# FlyballETS-MBD.net
KiCad netlist of a schematic drawn in EAGLE
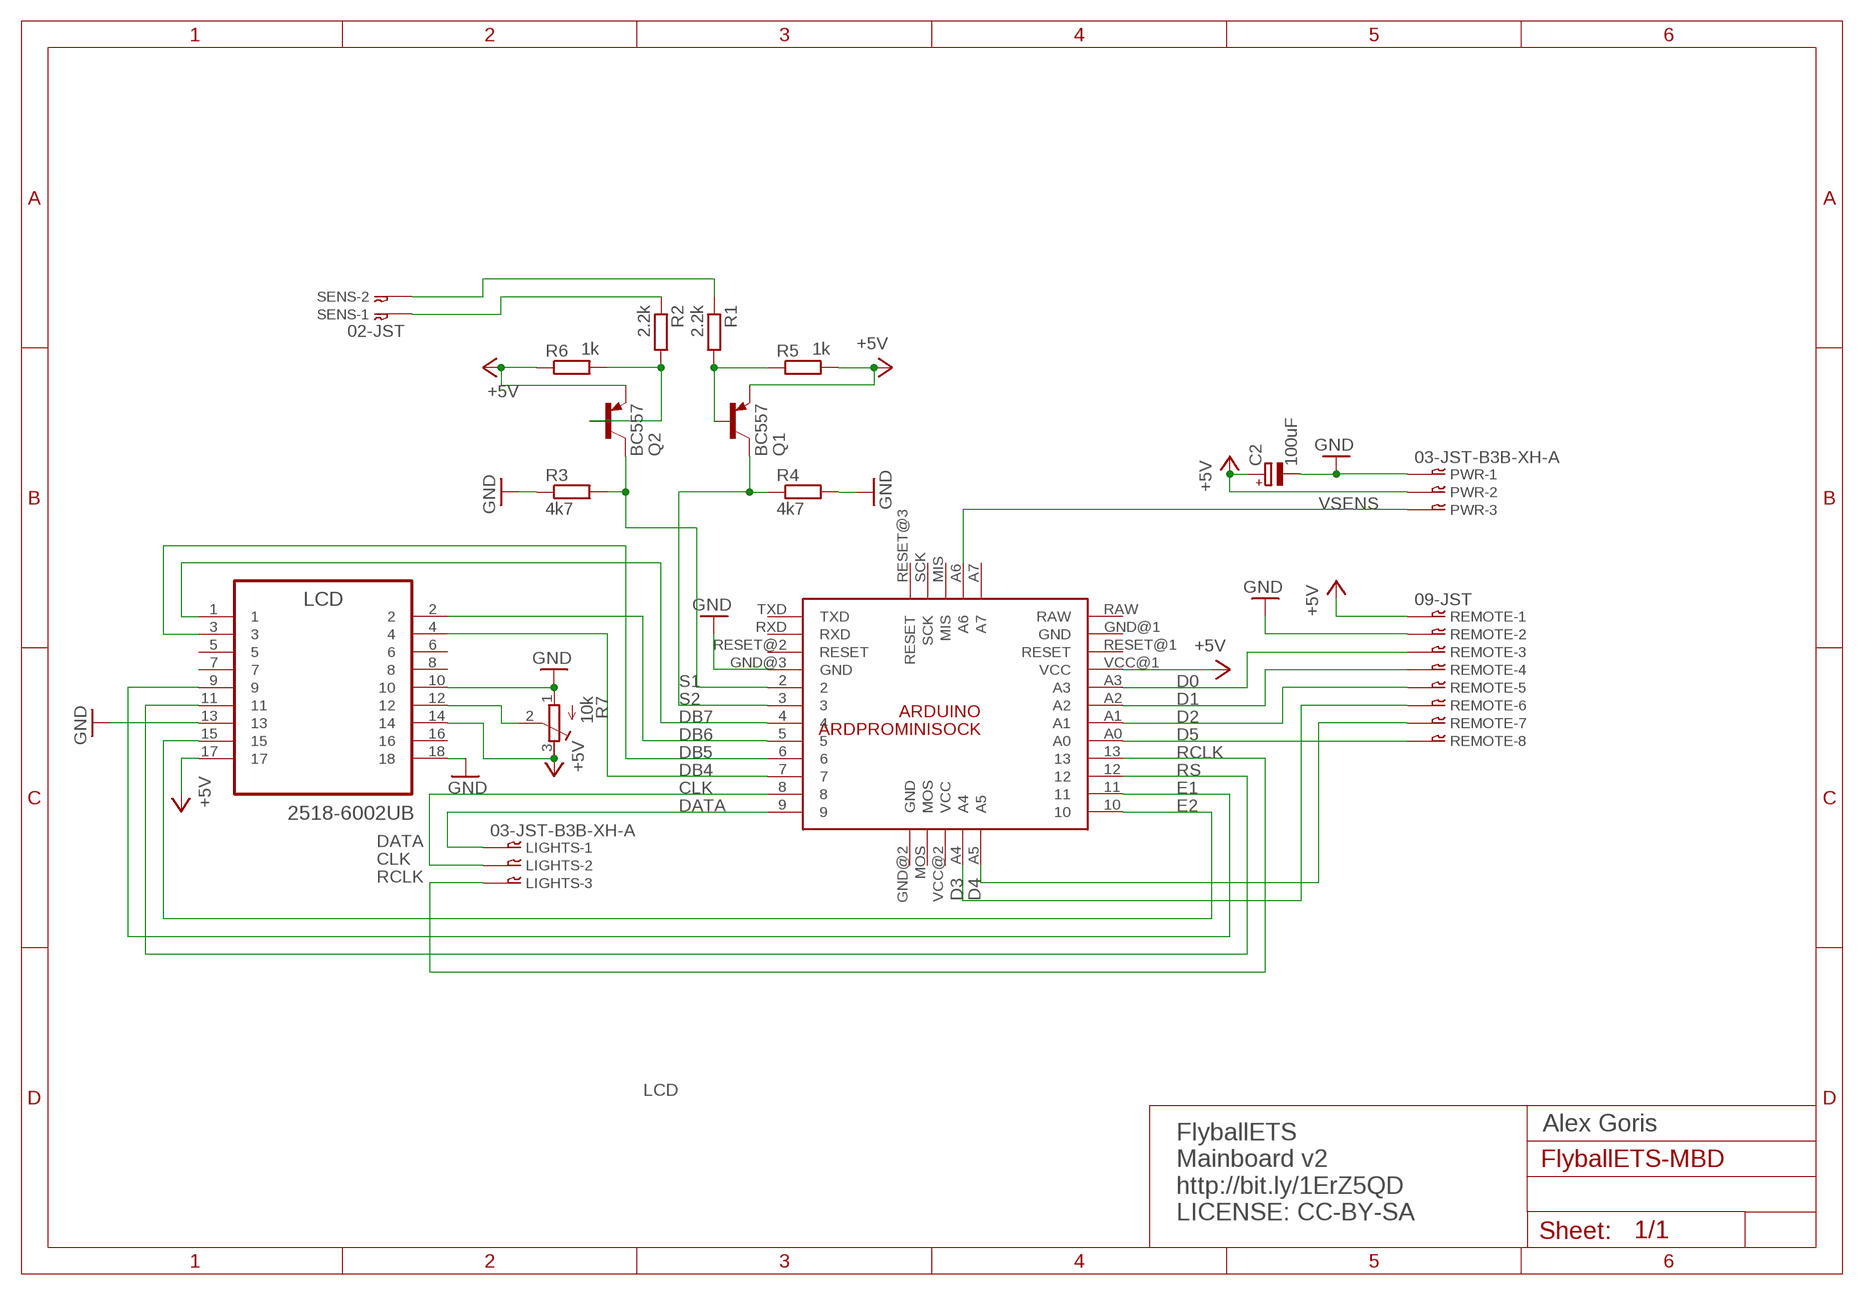
[diagram p0: schematic, sheet 1]

(export (version "E")
  (design (tool "Eeschema 10.0.6"))
  (components
    (comp (ref "ARDUINO")
      (value "ARDPROMINISOCK")
      (footprint "eagle-import:ARDPROMINISOCK")
      (libsource (lib "eagle-import") (part "ARDPROMINISOCK"))
    )
    (comp (ref "C2")
      (value "100uF")
      (footprint "eagle-import:E2,5-6E")
      (libsource (lib "eagle-import") (part "CPOL-EUE2,5-6E"))
    )
    (comp (ref "LCD")
      (value "2518-6002UB")
      (footprint "eagle-import:3M_2518-6002UB")
      (libsource (lib "eagle-import") (part "2518-6002UB"))
    )
    (comp (ref "LIGHTS")
      (value "03-JST-B3B-XH-A")
      (footprint "eagle-import:B3B-XH")
      (libsource (lib "eagle-import") (part "03-JST-B3B-XH-A"))
    )
    (comp (ref "PWR")
      (value "03-JST-B3B-XH-A")
      (footprint "eagle-import:B3B-XH")
      (libsource (lib "eagle-import") (part "03-JST-B3B-XH-A"))
    )
    (comp (ref "Q1")
      (value "BC557")
      (footprint "eagle-import:TO92")
      (libsource (lib "eagle-import") (part "BC557"))
    )
    (comp (ref "Q2")
      (value "BC557")
      (footprint "eagle-import:TO92")
      (libsource (lib "eagle-import") (part "BC557"))
    )
    (comp (ref "R1")
      (value "2.2k")
      (footprint "eagle-import:0207_10")
      (libsource (lib "eagle-import") (part "R-EU_0207/10"))
    )
    (comp (ref "R2")
      (value "2.2k")
      (footprint "eagle-import:0207_10")
      (libsource (lib "eagle-import") (part "R-EU_0207/10"))
    )
    (comp (ref "R3")
      (value "4k7")
      (footprint "eagle-import:0207_10")
      (libsource (lib "eagle-import") (part "R-EU_0207/10"))
    )
    (comp (ref "R4")
      (value "4k7")
      (footprint "eagle-import:0207_10")
      (libsource (lib "eagle-import") (part "R-EU_0207/10"))
    )
    (comp (ref "R5")
      (value "1k")
      (footprint "eagle-import:0207_10")
      (libsource (lib "eagle-import") (part "R-EU_0207/10"))
    )
    (comp (ref "R6")
      (value "1k")
      (footprint "eagle-import:0207_10")
      (libsource (lib "eagle-import") (part "R-EU_0207/10"))
    )
    (comp (ref "R7")
      (value "10k")
      (footprint "eagle-import:RTRIM3339P")
      (libsource (lib "eagle-import") (part "R-TRIMM3339P"))
    )
    (comp (ref "REMOTE")
      (value "09-JST")
      (footprint "eagle-import:B9B-XH")
      (libsource (lib "eagle-import") (part "09-JST"))
    )
    (comp (ref "SENS")
      (value "02-JST")
      (footprint "eagle-import:B2B-XH")
      (libsource (lib "eagle-import") (part "02-JST"))
    )
  )
  (nets
    (net (code "1") (name "+5V") (class "Default")
      (node (ref "ARDUINO") (pin "VCC@1") (pinfunction "VCC_VCC@1") (pintype "bidirectional"))
      (node (ref "C2") (pin "+") (pinfunction "+_+") (pintype "passive"))
      (node (ref "LCD") (pin "14") (pinfunction "14_14") (pintype "passive"))
      (node (ref "LCD") (pin "17") (pinfunction "17_17") (pintype "passive"))
      (node (ref "PWR") (pin "P$2") (pinfunction "1_P$2") (pintype "passive"))
      (node (ref "Q1") (pin "1") (pinfunction "E_1") (pintype "passive"))
      (node (ref "Q2") (pin "1") (pinfunction "E_1") (pintype "passive"))
      (node (ref "R5") (pin "2") (pinfunction "2_2") (pintype "passive"))
      (node (ref "R6") (pin "1") (pinfunction "1_1") (pintype "passive"))
      (node (ref "R7") (pin "3") (pinfunction "E_3") (pintype "passive"))
      (node (ref "REMOTE") (pin "P$1") (pinfunction "1_P$1") (pintype "passive"))
    )
    (net (code "2") (name "/CLK") (class "Default")
      (node (ref "ARDUINO") (pin "8") (pinfunction "8_8") (pintype "bidirectional"))
      (node (ref "LIGHTS") (pin "P$2") (pinfunction "1_P$2") (pintype "passive"))
    )
    (net (code "3") (name "/D0") (class "Default")
      (node (ref "ARDUINO") (pin "A3") (pinfunction "A3_A3") (pintype "bidirectional"))
      (node (ref "REMOTE") (pin "P$3") (pinfunction "1_P$3") (pintype "passive"))
    )
    (net (code "4") (name "/D1") (class "Default")
      (node (ref "ARDUINO") (pin "A2") (pinfunction "A2_A2") (pintype "bidirectional"))
      (node (ref "REMOTE") (pin "P$4") (pinfunction "1_P$4") (pintype "passive"))
    )
    (net (code "5") (name "/D2") (class "Default")
      (node (ref "ARDUINO") (pin "A1") (pinfunction "A1_A1") (pintype "bidirectional"))
      (node (ref "REMOTE") (pin "P$5") (pinfunction "1_P$5") (pintype "passive"))
    )
    (net (code "6") (name "/D3") (class "Default")
      (node (ref "ARDUINO") (pin "A4") (pinfunction "A4_A4") (pintype "bidirectional"))
      (node (ref "REMOTE") (pin "P$6") (pinfunction "1_P$6") (pintype "passive"))
    )
    (net (code "7") (name "/D4") (class "Default")
      (node (ref "ARDUINO") (pin "A5") (pinfunction "A5_A5") (pintype "bidirectional"))
      (node (ref "REMOTE") (pin "P$7") (pinfunction "1_P$7") (pintype "passive"))
    )
    (net (code "8") (name "/D5") (class "Default")
      (node (ref "ARDUINO") (pin "A0") (pinfunction "A0_A0") (pintype "bidirectional"))
      (node (ref "REMOTE") (pin "P$8") (pinfunction "1_P$8") (pintype "passive"))
    )
    (net (code "9") (name "/DATA") (class "Default")
      (node (ref "ARDUINO") (pin "9") (pinfunction "9_9") (pintype "bidirectional"))
      (node (ref "LIGHTS") (pin "P$1") (pinfunction "1_P$1") (pintype "passive"))
    )
    (net (code "10") (name "/DB4") (class "Default")
      (node (ref "ARDUINO") (pin "7") (pinfunction "7_7") (pintype "bidirectional"))
      (node (ref "LCD") (pin "4") (pinfunction "4_4") (pintype "passive"))
    )
    (net (code "11") (name "/DB5") (class "Default")
      (node (ref "ARDUINO") (pin "6") (pinfunction "6_6") (pintype "bidirectional"))
      (node (ref "LCD") (pin "3") (pinfunction "3_3") (pintype "passive"))
    )
    (net (code "12") (name "/DB6") (class "Default")
      (node (ref "ARDUINO") (pin "5") (pinfunction "5_5") (pintype "bidirectional"))
      (node (ref "LCD") (pin "2") (pinfunction "2_2") (pintype "passive"))
    )
    (net (code "13") (name "/DB7") (class "Default")
      (node (ref "ARDUINO") (pin "4") (pinfunction "4_4") (pintype "bidirectional"))
      (node (ref "LCD") (pin "1") (pinfunction "1_1") (pintype "passive"))
    )
    (net (code "14") (name "/E1") (class "Default")
      (node (ref "ARDUINO") (pin "11") (pinfunction "11_11") (pintype "bidirectional"))
      (node (ref "LCD") (pin "9") (pinfunction "9_9") (pintype "passive"))
    )
    (net (code "15") (name "/E2") (class "Default")
      (node (ref "ARDUINO") (pin "10") (pinfunction "10_10") (pintype "bidirectional"))
      (node (ref "LCD") (pin "15") (pinfunction "15_15") (pintype "passive"))
    )
    (net (code "16") (name "/RCLK") (class "Default")
      (node (ref "ARDUINO") (pin "13") (pinfunction "13_13") (pintype "bidirectional"))
      (node (ref "LIGHTS") (pin "P$3") (pinfunction "1_P$3") (pintype "passive"))
    )
    (net (code "17") (name "/RS") (class "Default")
      (node (ref "ARDUINO") (pin "12") (pinfunction "12_12") (pintype "bidirectional"))
      (node (ref "LCD") (pin "11") (pinfunction "11_11") (pintype "passive"))
    )
    (net (code "18") (name "/S1") (class "Default")
      (node (ref "ARDUINO") (pin "2") (pinfunction "2_2") (pintype "bidirectional"))
      (node (ref "Q2") (pin "3") (pinfunction "C_3") (pintype "passive"))
      (node (ref "R3") (pin "2") (pinfunction "2_2") (pintype "passive"))
    )
    (net (code "19") (name "/S2") (class "Default")
      (node (ref "ARDUINO") (pin "3") (pinfunction "3_3") (pintype "bidirectional"))
      (node (ref "Q1") (pin "3") (pinfunction "C_3") (pintype "passive"))
      (node (ref "R4") (pin "1") (pinfunction "1_1") (pintype "passive"))
    )
    (net (code "20") (name "/VSENS") (class "Default")
      (node (ref "ARDUINO") (pin "A6") (pinfunction "A6_A6") (pintype "bidirectional"))
      (node (ref "PWR") (pin "P$3") (pinfunction "1_P$3") (pintype "passive"))
    )
    (net (code "21") (name "GND") (class "Default")
      (node (ref "ARDUINO") (pin "GND@3") (pinfunction "GND_GND@3") (pintype "bidirectional"))
      (node (ref "C2") (pin "-") (pinfunction "-_-") (pintype "passive"))
      (node (ref "LCD") (pin "10") (pinfunction "10_10") (pintype "passive"))
      (node (ref "LCD") (pin "13") (pinfunction "13_13") (pintype "passive"))
      (node (ref "LCD") (pin "18") (pinfunction "18_18") (pintype "passive"))
      (node (ref "PWR") (pin "P$1") (pinfunction "1_P$1") (pintype "passive"))
      (node (ref "R3") (pin "1") (pinfunction "1_1") (pintype "passive"))
      (node (ref "R4") (pin "2") (pinfunction "2_2") (pintype "passive"))
      (node (ref "R7") (pin "1") (pinfunction "A_1") (pintype "passive"))
      (node (ref "REMOTE") (pin "P$2") (pinfunction "1_P$2") (pintype "passive"))
    )
    (net (code "22") (name "Net-(Q1-B)") (class "Default")
      (node (ref "Q1") (pin "2") (pinfunction "B_2") (pintype "passive"))
      (node (ref "R1") (pin "2") (pinfunction "2_2") (pintype "passive"))
      (node (ref "R5") (pin "1") (pinfunction "1_1") (pintype "passive"))
    )
    (net (code "23") (name "Net-(Q2-B)") (class "Default")
      (node (ref "Q2") (pin "2") (pinfunction "B_2") (pintype "passive"))
      (node (ref "R2") (pin "2") (pinfunction "2_2") (pintype "passive"))
      (node (ref "R6") (pin "2") (pinfunction "2_2") (pintype "passive"))
    )
    (net (code "24") (name "Net-(R7-S)") (class "Default")
      (node (ref "LCD") (pin "12") (pinfunction "12_12") (pintype "passive"))
      (node (ref "R7") (pin "2") (pinfunction "S_2") (pintype "passive"))
    )
    (net (code "25") (name "Net-(SENSA-1)") (class "Default")
      (node (ref "R2") (pin "1") (pinfunction "1_1") (pintype "passive"))
      (node (ref "SENS") (pin "P$1") (pinfunction "1_P$1") (pintype "passive"))
    )
    (net (code "26") (name "Net-(SENSB-1)") (class "Default")
      (node (ref "R1") (pin "1") (pinfunction "1_1") (pintype "passive"))
      (node (ref "SENS") (pin "P$2") (pinfunction "1_P$2") (pintype "passive"))
    )
    (net (code "27") (name "unconnected-(ARDUINO-GND-PadGND@1)") (class "Default")
      (node (ref "ARDUINO") (pin "GND@1") (pinfunction "GND_GND@1") (pintype "bidirectional"))
    )
    (net (code "28") (name "unconnected-(ARDUINO-GND-PadGND@2)") (class "Default")
      (node (ref "ARDUINO") (pin "GND@2") (pinfunction "GND_GND@2") (pintype "bidirectional"))
    )
    (net (code "29") (name "unconnected-(ARDUINO-PadA7)") (class "Default")
      (node (ref "ARDUINO") (pin "A7") (pinfunction "A7_A7") (pintype "bidirectional"))
    )
    (net (code "30") (name "unconnected-(ARDUINO-PadMIS)") (class "Default")
      (node (ref "ARDUINO") (pin "MIS") (pinfunction "MIS_MIS") (pintype "bidirectional"))
    )
    (net (code "31") (name "unconnected-(ARDUINO-PadMOS)") (class "Default")
      (node (ref "ARDUINO") (pin "MOS") (pinfunction "MOS_MOS") (pintype "bidirectional"))
    )
    (net (code "32") (name "unconnected-(ARDUINO-PadRAW)") (class "Default")
      (node (ref "ARDUINO") (pin "RAW") (pinfunction "RAW_RAW") (pintype "bidirectional"))
    )
    (net (code "33") (name "unconnected-(ARDUINO-PadRXD)") (class "Default")
      (node (ref "ARDUINO") (pin "RXD") (pinfunction "RXD_RXD") (pintype "bidirectional"))
    )
    (net (code "34") (name "unconnected-(ARDUINO-PadSCK)") (class "Default")
      (node (ref "ARDUINO") (pin "SCK") (pinfunction "SCK_SCK") (pintype "bidirectional"))
    )
    (net (code "35") (name "unconnected-(ARDUINO-PadTXD)") (class "Default")
      (node (ref "ARDUINO") (pin "TXD") (pinfunction "TXD_TXD") (pintype "bidirectional"))
    )
    (net (code "36") (name "unconnected-(ARDUINO-RESET-PadRESET@1)") (class "Default")
      (node (ref "ARDUINO") (pin "RESET@1") (pinfunction "RESET_RESET@1") (pintype "bidirectional"))
    )
    (net (code "37") (name "unconnected-(ARDUINO-RESET-PadRESET@2)") (class "Default")
      (node (ref "ARDUINO") (pin "RESET@2") (pinfunction "RESET_RESET@2") (pintype "bidirectional"))
    )
    (net (code "38") (name "unconnected-(ARDUINO-RESET-PadRESET@3)") (class "Default")
      (node (ref "ARDUINO") (pin "RESET@3") (pinfunction "RESET_RESET@3") (pintype "bidirectional"))
    )
    (net (code "39") (name "unconnected-(ARDUINO-VCC-PadVCC@2)") (class "Default")
      (node (ref "ARDUINO") (pin "VCC@2") (pinfunction "VCC_VCC@2") (pintype "bidirectional"))
    )
    (net (code "40") (name "unconnected-(LCD-Pad5)") (class "Default")
      (node (ref "LCD") (pin "5") (pinfunction "5_5") (pintype "passive"))
    )
    (net (code "41") (name "unconnected-(LCD-Pad6)") (class "Default")
      (node (ref "LCD") (pin "6") (pinfunction "6_6") (pintype "passive"))
    )
    (net (code "42") (name "unconnected-(LCD-Pad7)") (class "Default")
      (node (ref "LCD") (pin "7") (pinfunction "7_7") (pintype "passive"))
    )
    (net (code "43") (name "unconnected-(LCD-Pad8)") (class "Default")
      (node (ref "LCD") (pin "8") (pinfunction "8_8") (pintype "passive"))
    )
    (net (code "44") (name "unconnected-(LCD-Pad16)") (class "Default")
      (node (ref "LCD") (pin "16") (pinfunction "16_16") (pintype "passive"))
    )
  )
)
